# 12_-_CONNECTORS.net
KiCad netlist of a schematic drawn in Altium Designer
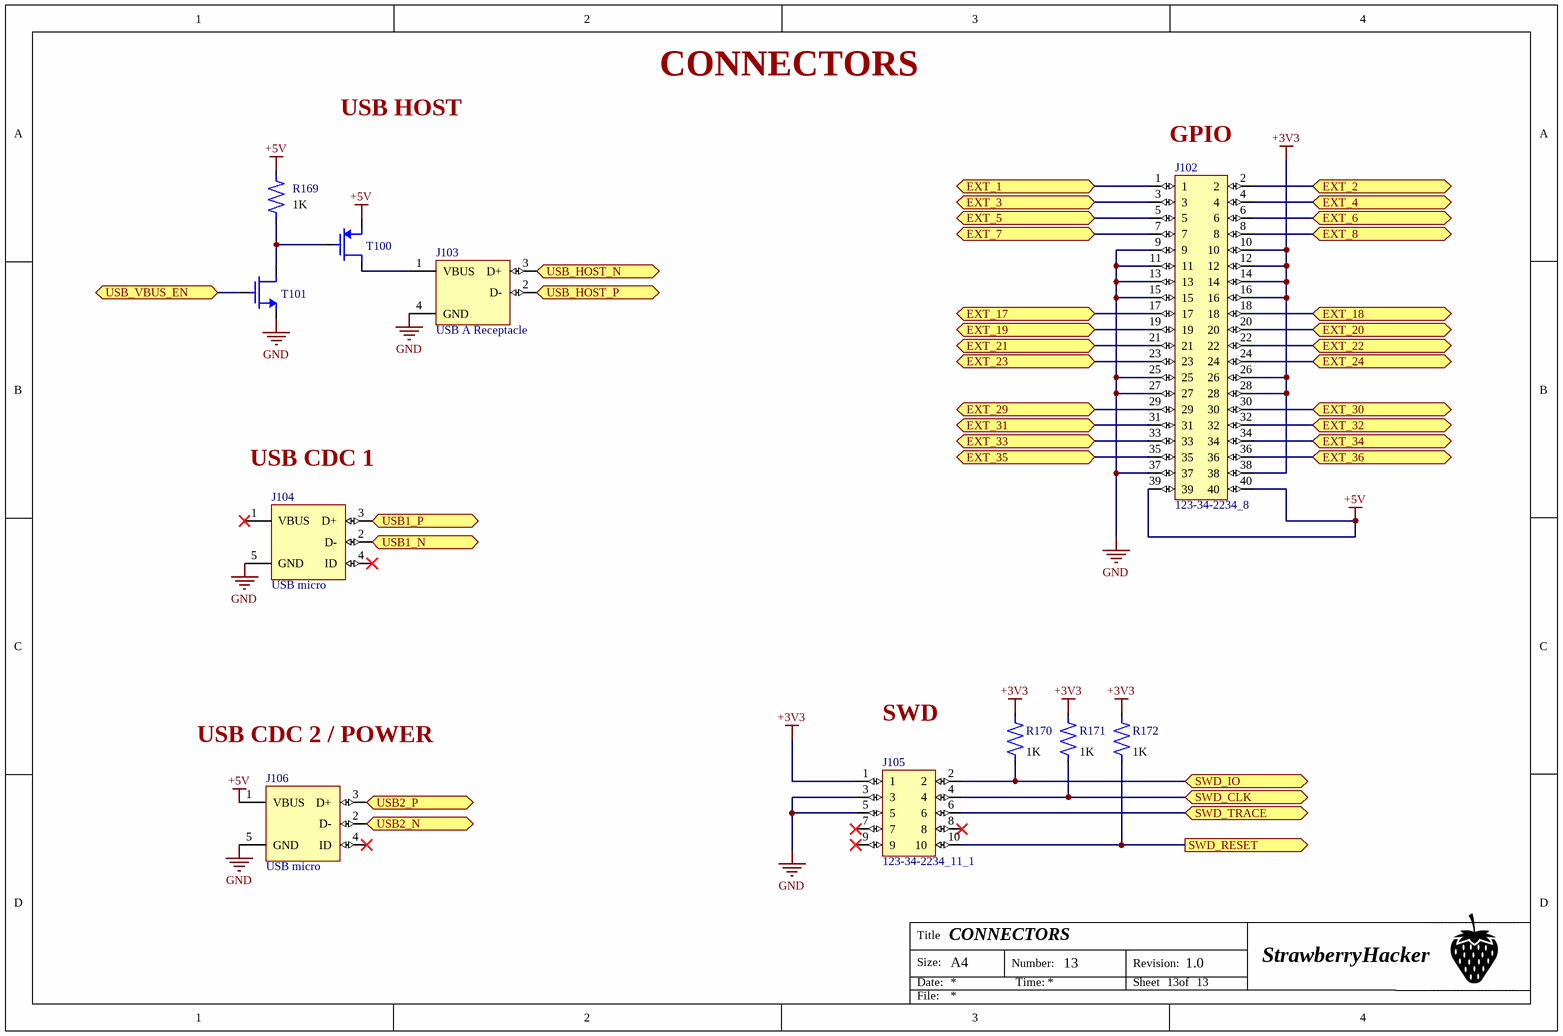
[diagram p0: [12] - CONNECTORS.SchDoc]

(export (version "E")
  (design (tool "Eeschema 10.0.6"))
  (components
    (comp (ref "J102")
      (value "123-34-2234_8")
      (footprint "Header 2x20 male")
      (description "Header 2x20 male 2.54mm")
      (libsource (lib "Connectors") (part "123-34-2234_8"))
    )
    (comp (ref "J103")
      (value "USB A Receptacle")
      (footprint "USB A Right angle")
      (description "USB A Right angle")
      (libsource (lib "Connectors") (part "MC32593_1"))
    )
    (comp (ref "J104")
      (value "USB micro")
      (footprint "USB micro")
      (description "USB B micro")
      (libsource (lib "Connectors") (part "47590-0001"))
    )
    (comp (ref "J105")
      (value "123-34-2234_11_1")
      (footprint "Header 2x5 male 1.27mm")
      (description "Header 2x5 male 1.27mm")
      (libsource (lib "Connectors") (part "123-34-2234_11_1"))
    )
    (comp (ref "J106")
      (value "USB micro")
      (footprint "USB micro")
      (description "USB B micro")
      (libsource (lib "Connectors") (part "47590-0001"))
    )
    (comp (ref "R169")
      (value "1K")
      (footprint "R0603")
      (description "R0603")
      (fields (field (name "Comment") "CPF-A-0603B100KE1"))
      (libsource (lib "Passive components") (part "CPF-A-0603B100KE1"))
    )
    (comp (ref "R170")
      (value "1K")
      (footprint "R0402")
      (description "R0402")
      (fields (field (name "Comment") "CRCW04020000Z0ED"))
      (libsource (lib "Passive components") (part "CRCW04020000Z0ED"))
    )
    (comp (ref "R171")
      (value "1K")
      (footprint "R0402")
      (description "R0402")
      (fields (field (name "Comment") "CRCW04020000Z0ED"))
      (libsource (lib "Passive components") (part "CRCW04020000Z0ED"))
    )
    (comp (ref "R172")
      (value "1K")
      (footprint "R0402")
      (description "R0402")
      (fields (field (name "Comment") "CRCW04020000Z0ED"))
      (libsource (lib "Passive components") (part "CRCW04020000Z0ED"))
    )
    (comp (ref "T100")
      (value "DMP1045U")
      (footprint "DMP1045U")
      (description "PMOS 5.2A -550mV")
      (libsource (lib "Transistors") (part "DMP1045U"))
    )
    (comp (ref "T101")
      (value "DMG6968U")
      (footprint "DMG6968U")
      (description "NMOS 6.5A 500mV")
      (libsource (lib "Transistors") (part "DMG6968U"))
    )
  )
  (nets
    (net (code "1") (name "+3V3") (class "Default")
      (node (ref "J102") (pin "10") (pinfunction "10_10") (pintype "bidirectional"))
      (node (ref "J102") (pin "12") (pinfunction "12_12") (pintype "bidirectional"))
      (node (ref "J102") (pin "14") (pinfunction "14_14") (pintype "bidirectional"))
      (node (ref "J102") (pin "16") (pinfunction "16_16") (pintype "bidirectional"))
      (node (ref "J102") (pin "26") (pinfunction "26_26") (pintype "bidirectional"))
      (node (ref "J102") (pin "28") (pinfunction "28_28") (pintype "bidirectional"))
      (node (ref "J102") (pin "38") (pinfunction "38_38") (pintype "bidirectional"))
      (node (ref "J105") (pin "1") (pinfunction "1_1") (pintype "bidirectional"))
      (node (ref "R170") (pin "2") (pinfunction "3_2") (pintype "passive"))
      (node (ref "R171") (pin "2") (pinfunction "3_2") (pintype "passive"))
      (node (ref "R172") (pin "2") (pinfunction "3_2") (pintype "passive"))
    )
    (net (code "2") (name "+5V") (class "Default")
      (node (ref "J102") (pin "39") (pinfunction "39_39") (pintype "bidirectional"))
      (node (ref "J102") (pin "40") (pinfunction "40_40") (pintype "bidirectional"))
      (node (ref "J106") (pin "1") (pinfunction "VBUS_1") (pintype "passive"))
      (node (ref "R169") (pin "2") (pinfunction "2_2") (pintype "passive"))
      (node (ref "T100") (pin "2") (pinfunction "S_2") (pintype "passive"))
    )
    (net (code "3") (name "/EXT_1") (class "Default")
      (node (ref "J102") (pin "1") (pinfunction "1_1") (pintype "bidirectional"))
    )
    (net (code "4") (name "/EXT_2") (class "Default")
      (node (ref "J102") (pin "2") (pinfunction "2_2") (pintype "bidirectional"))
    )
    (net (code "5") (name "/EXT_3") (class "Default")
      (node (ref "J102") (pin "3") (pinfunction "3_3") (pintype "bidirectional"))
    )
    (net (code "6") (name "/EXT_4") (class "Default")
      (node (ref "J102") (pin "4") (pinfunction "4_4") (pintype "bidirectional"))
    )
    (net (code "7") (name "/EXT_5") (class "Default")
      (node (ref "J102") (pin "5") (pinfunction "5_5") (pintype "bidirectional"))
    )
    (net (code "8") (name "/EXT_6") (class "Default")
      (node (ref "J102") (pin "6") (pinfunction "6_6") (pintype "bidirectional"))
    )
    (net (code "9") (name "/EXT_7") (class "Default")
      (node (ref "J102") (pin "7") (pinfunction "7_7") (pintype "bidirectional"))
    )
    (net (code "10") (name "/EXT_8") (class "Default")
      (node (ref "J102") (pin "8") (pinfunction "8_8") (pintype "bidirectional"))
    )
    (net (code "11") (name "/EXT_17") (class "Default")
      (node (ref "J102") (pin "17") (pinfunction "17_17") (pintype "bidirectional"))
    )
    (net (code "12") (name "/EXT_18") (class "Default")
      (node (ref "J102") (pin "18") (pinfunction "18_18") (pintype "bidirectional"))
    )
    (net (code "13") (name "/EXT_19") (class "Default")
      (node (ref "J102") (pin "19") (pinfunction "19_19") (pintype "bidirectional"))
    )
    (net (code "14") (name "/EXT_20") (class "Default")
      (node (ref "J102") (pin "20") (pinfunction "20_20") (pintype "bidirectional"))
    )
    (net (code "15") (name "/EXT_21") (class "Default")
      (node (ref "J102") (pin "21") (pinfunction "21_21") (pintype "bidirectional"))
    )
    (net (code "16") (name "/EXT_22") (class "Default")
      (node (ref "J102") (pin "22") (pinfunction "22_22") (pintype "bidirectional"))
    )
    (net (code "17") (name "/EXT_23") (class "Default")
      (node (ref "J102") (pin "23") (pinfunction "23_23") (pintype "bidirectional"))
    )
    (net (code "18") (name "/EXT_24") (class "Default")
      (node (ref "J102") (pin "24") (pinfunction "24_24") (pintype "bidirectional"))
    )
    (net (code "19") (name "/EXT_29") (class "Default")
      (node (ref "J102") (pin "29") (pinfunction "29_29") (pintype "bidirectional"))
    )
    (net (code "20") (name "/EXT_30") (class "Default")
      (node (ref "J102") (pin "30") (pinfunction "30_30") (pintype "bidirectional"))
    )
    (net (code "21") (name "/EXT_31") (class "Default")
      (node (ref "J102") (pin "31") (pinfunction "31_31") (pintype "bidirectional"))
    )
    (net (code "22") (name "/EXT_32") (class "Default")
      (node (ref "J102") (pin "32") (pinfunction "32_32") (pintype "bidirectional"))
    )
    (net (code "23") (name "/EXT_33") (class "Default")
      (node (ref "J102") (pin "33") (pinfunction "33_33") (pintype "bidirectional"))
    )
    (net (code "24") (name "/EXT_34") (class "Default")
      (node (ref "J102") (pin "34") (pinfunction "34_34") (pintype "bidirectional"))
    )
    (net (code "25") (name "/EXT_35") (class "Default")
      (node (ref "J102") (pin "35") (pinfunction "35_35") (pintype "bidirectional"))
    )
    (net (code "26") (name "/EXT_36") (class "Default")
      (node (ref "J102") (pin "36") (pinfunction "36_36") (pintype "bidirectional"))
    )
    (net (code "27") (name "/SWD_CLK") (class "Default")
      (node (ref "J105") (pin "4") (pinfunction "4_4") (pintype "bidirectional"))
      (node (ref "R171") (pin "1") (pinfunction "1_1") (pintype "passive"))
    )
    (net (code "28") (name "/SWD_IO") (class "Default")
      (node (ref "J105") (pin "2") (pinfunction "2_2") (pintype "bidirectional"))
      (node (ref "R170") (pin "1") (pinfunction "1_1") (pintype "passive"))
    )
    (net (code "29") (name "/SWD_RESET") (class "Default")
      (node (ref "J105") (pin "10") (pinfunction "10_10") (pintype "bidirectional"))
      (node (ref "R172") (pin "1") (pinfunction "1_1") (pintype "passive"))
    )
    (net (code "30") (name "/SWD_TRACE") (class "Default")
      (node (ref "J105") (pin "6") (pinfunction "6_6") (pintype "bidirectional"))
    )
    (net (code "31") (name "/USB1_N") (class "Default")
      (node (ref "J104") (pin "2") (pinfunction "D-_2") (pintype "bidirectional"))
    )
    (net (code "32") (name "/USB1_P") (class "Default")
      (node (ref "J104") (pin "3") (pinfunction "D+_3") (pintype "bidirectional"))
    )
    (net (code "33") (name "/USB2_N") (class "Default")
      (node (ref "J106") (pin "2") (pinfunction "D-_2") (pintype "bidirectional"))
    )
    (net (code "34") (name "/USB2_P") (class "Default")
      (node (ref "J106") (pin "3") (pinfunction "D+_3") (pintype "bidirectional"))
    )
    (net (code "35") (name "/USB_HOST_N") (class "Default")
      (node (ref "J103") (pin "3") (pinfunction "D+_3") (pintype "bidirectional"))
    )
    (net (code "36") (name "/USB_HOST_P") (class "Default")
      (node (ref "J103") (pin "2") (pinfunction "D-_2") (pintype "bidirectional"))
    )
    (net (code "37") (name "/USB_VBUS_EN") (class "Default")
      (node (ref "T101") (pin "1") (pinfunction "G_1") (pintype "passive"))
    )
    (net (code "38") (name "GND") (class "Default")
      (node (ref "J102") (pin "11") (pinfunction "11_11") (pintype "bidirectional"))
      (node (ref "J102") (pin "13") (pinfunction "13_13") (pintype "bidirectional"))
      (node (ref "J102") (pin "15") (pinfunction "15_15") (pintype "bidirectional"))
      (node (ref "J102") (pin "25") (pinfunction "25_25") (pintype "bidirectional"))
      (node (ref "J102") (pin "27") (pinfunction "27_27") (pintype "bidirectional"))
      (node (ref "J102") (pin "37") (pinfunction "37_37") (pintype "bidirectional"))
      (node (ref "J102") (pin "9") (pinfunction "9_9") (pintype "bidirectional"))
      (node (ref "J103") (pin "4") (pinfunction "GND_4") (pintype "passive"))
      (node (ref "J104") (pin "5") (pinfunction "GND_5") (pintype "passive"))
      (node (ref "J105") (pin "3") (pinfunction "3_3") (pintype "bidirectional"))
      (node (ref "J105") (pin "5") (pinfunction "5_5") (pintype "bidirectional"))
      (node (ref "J106") (pin "5") (pinfunction "GND_5") (pintype "passive"))
      (node (ref "T101") (pin "2") (pinfunction "S_2") (pintype "passive"))
    )
    (net (code "39") (name "Net-(J103-VBUS)") (class "Default")
      (node (ref "J103") (pin "1") (pinfunction "VBUS_1") (pintype "passive"))
      (node (ref "T100") (pin "3") (pinfunction "D_3") (pintype "passive"))
    )
    (net (code "40") (name "Net-(T100-G)") (class "Default")
      (node (ref "R169") (pin "1") (pinfunction "1_1") (pintype "passive"))
      (node (ref "T100") (pin "1") (pinfunction "G_1") (pintype "passive"))
      (node (ref "T101") (pin "3") (pinfunction "D_3") (pintype "passive"))
    )
    (net (code "41") (name "unconnected-(J104-ID-Pad4)") (class "Default")
      (node (ref "J104") (pin "4") (pinfunction "ID_4") (pintype "bidirectional+no_connect"))
    )
    (net (code "42") (name "unconnected-(J104-VBUS-Pad1)") (class "Default")
      (node (ref "J104") (pin "1") (pinfunction "VBUS_1") (pintype "passive+no_connect"))
    )
    (net (code "43") (name "unconnected-(J105-Pad7)") (class "Default")
      (node (ref "J105") (pin "7") (pinfunction "7_7") (pintype "bidirectional+no_connect"))
    )
    (net (code "44") (name "unconnected-(J105-Pad8)") (class "Default")
      (node (ref "J105") (pin "8") (pinfunction "8_8") (pintype "bidirectional+no_connect"))
    )
    (net (code "45") (name "unconnected-(J105-Pad9)") (class "Default")
      (node (ref "J105") (pin "9") (pinfunction "9_9") (pintype "bidirectional+no_connect"))
    )
    (net (code "46") (name "unconnected-(J106-ID-Pad4)") (class "Default")
      (node (ref "J106") (pin "4") (pinfunction "ID_4") (pintype "bidirectional+no_connect"))
    )
  )
)
